# ESPOAT.net
KiCad netlist of a schematic drawn in EAGLE
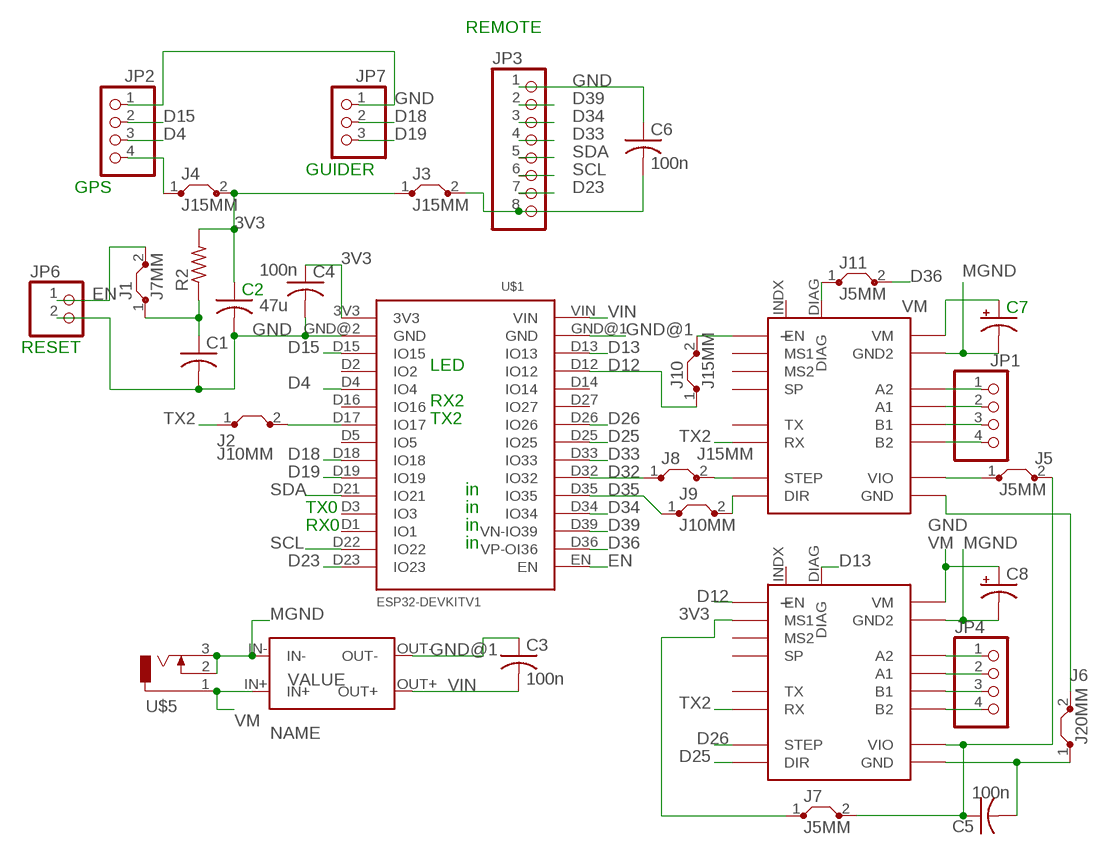
[diagram p0: schematic, sheet 1]

(export (version "E")
  (design (tool "Eeschema 10.0.6"))
  (components
    (comp (ref "C1")
      (value "C-US025-030X050")
      (footprint "eagle-import:C025-030X050")
      (libsource (lib "eagle-import") (part "C-US025-030X050"))
    )
    (comp (ref "C2")
      (value "47u")
      (footprint "eagle-import:C050-024X044")
      (libsource (lib "eagle-import") (part "C-US050-024X044"))
    )
    (comp (ref "C3")
      (value "100n")
      (footprint "eagle-import:C050-024X044")
      (libsource (lib "eagle-import") (part "C-US050-024X044"))
    )
    (comp (ref "C4")
      (value "100n")
      (footprint "eagle-import:C050-024X044")
      (libsource (lib "eagle-import") (part "C-US050-024X044"))
    )
    (comp (ref "C5")
      (value "100n")
      (footprint "eagle-import:C050-024X044")
      (libsource (lib "eagle-import") (part "C-US050-024X044"))
    )
    (comp (ref "C6")
      (value "100n")
      (footprint "eagle-import:C050-024X044")
      (libsource (lib "eagle-import") (part "C-US050-024X044"))
    )
    (comp (ref "C7")
      (value "CPOL-USE5-8.5")
      (footprint "eagle-import:E5-8,5")
      (libsource (lib "eagle-import") (part "CPOL-USE5-8.5"))
    )
    (comp (ref "C8")
      (value "CPOL-USE5-8.5")
      (footprint "eagle-import:E5-8,5")
      (libsource (lib "eagle-import") (part "CPOL-USE5-8.5"))
    )
    (comp (ref "J1")
      (value "J7MM")
      (footprint "eagle-import:07")
      (libsource (lib "eagle-import") (part "J7MM"))
    )
    (comp (ref "J2")
      (value "J10MM")
      (footprint "eagle-import:10")
      (libsource (lib "eagle-import") (part "J10MM"))
    )
    (comp (ref "J3")
      (value "J15MM")
      (footprint "eagle-import:15")
      (libsource (lib "eagle-import") (part "J15MM"))
    )
    (comp (ref "J4")
      (value "J15MM")
      (footprint "eagle-import:15")
      (libsource (lib "eagle-import") (part "J15MM"))
    )
    (comp (ref "J5")
      (value "J5MM")
      (footprint "eagle-import:05")
      (libsource (lib "eagle-import") (part "J5MM"))
    )
    (comp (ref "J6")
      (value "J20MM")
      (footprint "eagle-import:20")
      (libsource (lib "eagle-import") (part "J20MM"))
    )
    (comp (ref "J7")
      (value "J5MM")
      (footprint "eagle-import:05")
      (libsource (lib "eagle-import") (part "J5MM"))
    )
    (comp (ref "J8")
      (value "J15MM")
      (footprint "eagle-import:15")
      (libsource (lib "eagle-import") (part "J15MM"))
    )
    (comp (ref "J9")
      (value "J10MM")
      (footprint "eagle-import:10")
      (libsource (lib "eagle-import") (part "J10MM"))
    )
    (comp (ref "J10")
      (value "J15MM")
      (footprint "eagle-import:15")
      (libsource (lib "eagle-import") (part "J15MM"))
    )
    (comp (ref "J11")
      (value "J5MM")
      (footprint "eagle-import:05")
      (libsource (lib "eagle-import") (part "J5MM"))
    )
    (comp (ref "JP1")
      (value "PINHD-1X4")
      (footprint "eagle-import:1X04")
      (libsource (lib "eagle-import") (part "PINHD-1X4"))
    )
    (comp (ref "JP2")
      (value "PINHD-1X4")
      (footprint "eagle-import:1X04")
      (libsource (lib "eagle-import") (part "PINHD-1X4"))
    )
    (comp (ref "JP3")
      (value "PINHD-1X8")
      (footprint "eagle-import:1X08")
      (libsource (lib "eagle-import") (part "PINHD-1X8"))
    )
    (comp (ref "JP4")
      (value "PINHD-1X4")
      (footprint "eagle-import:1X04")
      (libsource (lib "eagle-import") (part "PINHD-1X4"))
    )
    (comp (ref "JP6")
      (value "PINHD-1X2")
      (footprint "eagle-import:1X02")
      (libsource (lib "eagle-import") (part "PINHD-1X2"))
    )
    (comp (ref "JP7")
      (value "PINHD-1X3")
      (footprint "eagle-import:1X03")
      (libsource (lib "eagle-import") (part "PINHD-1X3"))
    )
    (comp (ref "R2")
      (value "R-US_0207/10")
      (footprint "eagle-import:0207_10")
      (libsource (lib "eagle-import") (part "R-US_0207/10"))
    )
    (comp (ref "U$1")
      (value "ESP32DEVKITV1")
      (footprint "eagle-import:ESP32-DEVKITV1")
      (libsource (lib "eagle-import") (part "ESP32DEVKITV1"))
    )
    (comp (ref "U$2")
      (value "FY2209V3")
      (footprint "eagle-import:FY2209V3")
      (libsource (lib "eagle-import") (part "FY2209V3"))
    )
    (comp (ref "U$3")
      (value "FY2209V3")
      (footprint "eagle-import:FY2209V3")
      (libsource (lib "eagle-import") (part "FY2209V3"))
    )
    (comp (ref "U$4")
      (value "MINI-360")
      (footprint "eagle-import:MINI-360")
      (libsource (lib "eagle-import") (part "MINI-360"))
    )
    (comp (ref "U$5")
      (value "PS0520")
      (footprint "eagle-import:DCJ0203")
      (libsource (lib "eagle-import") (part "PS0520"))
    )
  )
  (nets
    (net (code "1") (name "/3V3") (class "Default")
      (node (ref "C2") (pin "1") (pinfunction "1_1") (pintype "passive"))
      (node (ref "C4") (pin "1") (pinfunction "1_1") (pintype "passive"))
      (node (ref "J3") (pin "1") (pinfunction "1_1") (pintype "passive"))
      (node (ref "J4") (pin "2") (pinfunction "2_2") (pintype "passive"))
      (node (ref "J7") (pin "1") (pinfunction "1_1") (pintype "passive"))
      (node (ref "R2") (pin "2") (pinfunction "2_2") (pintype "passive"))
      (node (ref "U$1") (pin "3V3") (pinfunction "3V3_3V3") (pintype "bidirectional"))
      (node (ref "U$3") (pin "MS1") (pinfunction "MS1_MS1") (pintype "bidirectional"))
    )
    (net (code "2") (name "/D4") (class "Default")
      (node (ref "JP2") (pin "3") (pinfunction "3_3") (pintype "passive"))
      (node (ref "U$1") (pin "D4") (pinfunction "IO4_D4") (pintype "bidirectional"))
    )
    (net (code "3") (name "/D12") (class "Default")
      (node (ref "J10") (pin "1") (pinfunction "1_1") (pintype "passive"))
      (node (ref "U$1") (pin "D12") (pinfunction "IO12_D12") (pintype "bidirectional"))
      (node (ref "U$3") (pin "EN") (pinfunction "EN_EN") (pintype "bidirectional"))
    )
    (net (code "4") (name "/D13") (class "Default")
      (node (ref "U$1") (pin "D13") (pinfunction "IO13_D13") (pintype "bidirectional"))
      (node (ref "U$3") (pin "DIAG") (pinfunction "DIAG_DIAG") (pintype "bidirectional"))
    )
    (net (code "5") (name "/D15") (class "Default")
      (node (ref "JP2") (pin "2") (pinfunction "2_2") (pintype "passive"))
      (node (ref "U$1") (pin "D15") (pinfunction "IO15_D15") (pintype "bidirectional"))
    )
    (net (code "6") (name "/D18") (class "Default")
      (node (ref "JP7") (pin "2") (pinfunction "2_2") (pintype "passive"))
      (node (ref "U$1") (pin "D18") (pinfunction "IO18_D18") (pintype "bidirectional"))
    )
    (net (code "7") (name "/D19") (class "Default")
      (node (ref "JP7") (pin "3") (pinfunction "3_3") (pintype "passive"))
      (node (ref "U$1") (pin "D19") (pinfunction "IO19_D19") (pintype "bidirectional"))
    )
    (net (code "8") (name "/D23") (class "Default")
      (node (ref "JP3") (pin "7") (pinfunction "7_7") (pintype "passive"))
      (node (ref "U$1") (pin "D23") (pinfunction "IO23_D23") (pintype "bidirectional"))
    )
    (net (code "9") (name "/D25") (class "Default")
      (node (ref "U$1") (pin "D25") (pinfunction "IO25_D25") (pintype "bidirectional"))
      (node (ref "U$3") (pin "DIR") (pinfunction "DIR_DIR") (pintype "bidirectional"))
    )
    (net (code "10") (name "/D26") (class "Default")
      (node (ref "U$1") (pin "D26") (pinfunction "IO26_D26") (pintype "bidirectional"))
      (node (ref "U$3") (pin "STP") (pinfunction "STEP_STP") (pintype "bidirectional"))
    )
    (net (code "11") (name "/D32") (class "Default")
      (node (ref "J8") (pin "1") (pinfunction "1_1") (pintype "passive"))
      (node (ref "U$1") (pin "D32") (pinfunction "IO32_D32") (pintype "bidirectional"))
    )
    (net (code "12") (name "/D33") (class "Default")
      (node (ref "JP3") (pin "4") (pinfunction "4_4") (pintype "passive"))
      (node (ref "U$1") (pin "D33") (pinfunction "IO33_D33") (pintype "bidirectional"))
    )
    (net (code "13") (name "/D34") (class "Default")
      (node (ref "JP3") (pin "3") (pinfunction "3_3") (pintype "passive"))
      (node (ref "U$1") (pin "D34") (pinfunction "IO34_D34") (pintype "bidirectional"))
    )
    (net (code "14") (name "/D35") (class "Default")
      (node (ref "J9") (pin "1") (pinfunction "1_1") (pintype "passive"))
      (node (ref "U$1") (pin "D35") (pinfunction "IO35_D35") (pintype "bidirectional"))
    )
    (net (code "15") (name "/D36") (class "Default")
      (node (ref "J11") (pin "2") (pinfunction "2_2") (pintype "passive"))
      (node (ref "U$1") (pin "D36") (pinfunction "VP-OI36_D36") (pintype "bidirectional"))
    )
    (net (code "16") (name "/D39") (class "Default")
      (node (ref "JP3") (pin "2") (pinfunction "2_2") (pintype "passive"))
      (node (ref "U$1") (pin "D39") (pinfunction "VN-IO39_D39") (pintype "bidirectional"))
    )
    (net (code "17") (name "/EN") (class "Default")
      (node (ref "J1") (pin "2") (pinfunction "2_2") (pintype "passive"))
      (node (ref "JP6") (pin "1") (pinfunction "1_1") (pintype "passive"))
      (node (ref "U$1") (pin "EN") (pinfunction "EN_EN") (pintype "bidirectional"))
    )
    (net (code "18") (name "/GND") (class "Default")
      (node (ref "C1") (pin "2") (pinfunction "2_2") (pintype "passive"))
      (node (ref "C2") (pin "2") (pinfunction "2_2") (pintype "passive"))
      (node (ref "C4") (pin "2") (pinfunction "2_2") (pintype "passive"))
      (node (ref "C6") (pin "1") (pinfunction "1_1") (pintype "passive"))
      (node (ref "J6") (pin "2") (pinfunction "2_2") (pintype "passive"))
      (node (ref "JP2") (pin "1") (pinfunction "1_1") (pintype "passive"))
      (node (ref "JP3") (pin "1") (pinfunction "1_1") (pintype "passive"))
      (node (ref "JP6") (pin "2") (pinfunction "2_2") (pintype "passive"))
      (node (ref "JP7") (pin "1") (pinfunction "1_1") (pintype "passive"))
      (node (ref "U$1") (pin "GND@2") (pinfunction "GND_GND@2") (pintype "bidirectional"))
      (node (ref "U$2") (pin "GND") (pinfunction "GND_GND") (pintype "bidirectional"))
    )
    (net (code "19") (name "/GND@1") (class "Default")
      (node (ref "C3") (pin "1") (pinfunction "1_1") (pintype "passive"))
      (node (ref "U$1") (pin "GND@1") (pinfunction "GND_GND@1") (pintype "bidirectional"))
      (node (ref "U$4") (pin "OUT-") (pinfunction "OUT-_OUT-") (pintype "output"))
    )
    (net (code "20") (name "/MGND") (class "Default")
      (node (ref "C7") (pin "-") (pinfunction "-_-") (pintype "passive"))
      (node (ref "C8") (pin "-") (pinfunction "-_-") (pintype "passive"))
      (node (ref "U$2") (pin "GND2") (pinfunction "GND2_GND2") (pintype "bidirectional"))
      (node (ref "U$3") (pin "GND2") (pinfunction "GND2_GND2") (pintype "bidirectional"))
      (node (ref "U$4") (pin "IN-") (pinfunction "IN-_IN-") (pintype "input"))
      (node (ref "U$5") (pin "2") (pinfunction "2_2") (pintype "passive"))
      (node (ref "U$5") (pin "3") (pinfunction "3_3") (pintype "passive"))
    )
    (net (code "21") (name "/SCL") (class "Default")
      (node (ref "JP3") (pin "6") (pinfunction "6_6") (pintype "passive"))
      (node (ref "U$1") (pin "D22") (pinfunction "IO22_D22") (pintype "bidirectional"))
    )
    (net (code "22") (name "/SDA") (class "Default")
      (node (ref "JP3") (pin "5") (pinfunction "5_5") (pintype "passive"))
      (node (ref "U$1") (pin "D21") (pinfunction "IO21_D21") (pintype "bidirectional"))
    )
    (net (code "23") (name "/TX2") (class "Default")
      (node (ref "J2") (pin "1") (pinfunction "1_1") (pintype "passive"))
      (node (ref "U$2") (pin "RX") (pinfunction "RX_RX") (pintype "bidirectional"))
      (node (ref "U$3") (pin "RX") (pinfunction "RX_RX") (pintype "bidirectional"))
    )
    (net (code "24") (name "/VIN") (class "Default")
      (node (ref "C3") (pin "2") (pinfunction "2_2") (pintype "passive"))
      (node (ref "U$1") (pin "VIN") (pinfunction "VIN_VIN") (pintype "bidirectional"))
      (node (ref "U$4") (pin "OUT+") (pinfunction "OUT+_OUT+") (pintype "output"))
    )
    (net (code "25") (name "/VM") (class "Default")
      (node (ref "C7") (pin "+") (pinfunction "+_+") (pintype "passive"))
      (node (ref "C8") (pin "+") (pinfunction "+_+") (pintype "passive"))
      (node (ref "U$2") (pin "VM") (pinfunction "VM_VM") (pintype "bidirectional"))
      (node (ref "U$3") (pin "VM") (pinfunction "VM_VM") (pintype "bidirectional"))
      (node (ref "U$4") (pin "IN+") (pinfunction "IN+_IN+") (pintype "input"))
      (node (ref "U$5") (pin "1") (pinfunction "1_1") (pintype "passive"))
    )
    (net (code "26") (name "Net-(C1-Pad1)") (class "Default")
      (node (ref "C1") (pin "1") (pinfunction "1_1") (pintype "passive"))
      (node (ref "J1") (pin "1") (pinfunction "1_1") (pintype "passive"))
      (node (ref "R2") (pin "1") (pinfunction "1_1") (pintype "passive"))
    )
    (net (code "27") (name "Net-(C5-Pad1)") (class "Default")
      (node (ref "C5") (pin "1") (pinfunction "1_1") (pintype "passive"))
      (node (ref "J5") (pin "2") (pinfunction "2_2") (pintype "passive"))
      (node (ref "J7") (pin "2") (pinfunction "2_2") (pintype "passive"))
      (node (ref "U$3") (pin "VIO") (pinfunction "VIO_VIO") (pintype "bidirectional"))
    )
    (net (code "28") (name "Net-(C5-Pad2)") (class "Default")
      (node (ref "C5") (pin "2") (pinfunction "2_2") (pintype "passive"))
      (node (ref "J6") (pin "1") (pinfunction "1_1") (pintype "passive"))
      (node (ref "U$3") (pin "GND") (pinfunction "GND_GND") (pintype "bidirectional"))
    )
    (net (code "29") (name "Net-(C6-Pad2)") (class "Default")
      (node (ref "C6") (pin "2") (pinfunction "2_2") (pintype "passive"))
      (node (ref "J3") (pin "2") (pinfunction "2_2") (pintype "passive"))
      (node (ref "JP3") (pin "8") (pinfunction "8_8") (pintype "passive"))
    )
    (net (code "30") (name "Net-(J4-Pad1)") (class "Default")
      (node (ref "J4") (pin "1") (pinfunction "1_1") (pintype "passive"))
      (node (ref "JP2") (pin "4") (pinfunction "4_4") (pintype "passive"))
    )
    (net (code "31") (name "Net-(J5-Pad1)") (class "Default")
      (node (ref "J5") (pin "1") (pinfunction "1_1") (pintype "passive"))
      (node (ref "U$2") (pin "VIO") (pinfunction "VIO_VIO") (pintype "bidirectional"))
    )
    (net (code "32") (name "Net-(J9-Pad2)") (class "Default")
      (node (ref "J9") (pin "2") (pinfunction "2_2") (pintype "passive"))
      (node (ref "U$2") (pin "DIR") (pinfunction "DIR_DIR") (pintype "bidirectional"))
    )
    (net (code "33") (name "Net-(J10-Pad2)") (class "Default")
      (node (ref "J10") (pin "2") (pinfunction "2_2") (pintype "passive"))
      (node (ref "U$2") (pin "EN") (pinfunction "EN_EN") (pintype "bidirectional"))
    )
    (net (code "34") (name "Net-(J11-Pad1)") (class "Default")
      (node (ref "J11") (pin "1") (pinfunction "1_1") (pintype "passive"))
      (node (ref "U$2") (pin "DIAG") (pinfunction "DIAG_DIAG") (pintype "bidirectional"))
    )
    (net (code "35") (name "Net-(JP1-Pad1)") (class "Default")
      (node (ref "JP1") (pin "1") (pinfunction "1_1") (pintype "passive"))
      (node (ref "U$2") (pin "A2") (pinfunction "A2_A2") (pintype "bidirectional"))
    )
    (net (code "36") (name "Net-(JP1-Pad2)") (class "Default")
      (node (ref "JP1") (pin "2") (pinfunction "2_2") (pintype "passive"))
      (node (ref "U$2") (pin "A1") (pinfunction "A1_A1") (pintype "bidirectional"))
    )
    (net (code "37") (name "Net-(JP1-Pad3)") (class "Default")
      (node (ref "JP1") (pin "3") (pinfunction "3_3") (pintype "passive"))
      (node (ref "U$2") (pin "B1") (pinfunction "B1_B1") (pintype "bidirectional"))
    )
    (net (code "38") (name "Net-(JP1-Pad4)") (class "Default")
      (node (ref "JP1") (pin "4") (pinfunction "4_4") (pintype "passive"))
      (node (ref "U$2") (pin "B2") (pinfunction "B2_B2") (pintype "bidirectional"))
    )
    (net (code "39") (name "Net-(JP4-Pad1)") (class "Default")
      (node (ref "JP4") (pin "1") (pinfunction "1_1") (pintype "passive"))
      (node (ref "U$3") (pin "A2") (pinfunction "A2_A2") (pintype "bidirectional"))
    )
    (net (code "40") (name "Net-(JP4-Pad2)") (class "Default")
      (node (ref "JP4") (pin "2") (pinfunction "2_2") (pintype "passive"))
      (node (ref "U$3") (pin "A1") (pinfunction "A1_A1") (pintype "bidirectional"))
    )
    (net (code "41") (name "Net-(JP4-Pad3)") (class "Default")
      (node (ref "JP4") (pin "3") (pinfunction "3_3") (pintype "passive"))
      (node (ref "U$3") (pin "B1") (pinfunction "B1_B1") (pintype "bidirectional"))
    )
    (net (code "42") (name "Net-(JP4-Pad4)") (class "Default")
      (node (ref "JP4") (pin "4") (pinfunction "4_4") (pintype "passive"))
      (node (ref "U$3") (pin "B2") (pinfunction "B2_B2") (pintype "bidirectional"))
    )
    (net (code "43") (name "Net-(U$1-IO17)") (class "Default")
      (node (ref "J2") (pin "2") (pinfunction "2_2") (pintype "passive"))
      (node (ref "U$1") (pin "D17") (pinfunction "IO17_D17") (pintype "bidirectional"))
    )
    (net (code "44") (name "Net-(U$2-STEP)") (class "Default")
      (node (ref "J8") (pin "2") (pinfunction "2_2") (pintype "passive"))
      (node (ref "U$2") (pin "STP") (pinfunction "STEP_STP") (pintype "bidirectional"))
    )
    (net (code "45") (name "unconnected-(U$1-IO1-PadD1)") (class "Default")
      (node (ref "U$1") (pin "D1") (pinfunction "IO1_D1") (pintype "bidirectional"))
    )
    (net (code "46") (name "unconnected-(U$1-IO2-PadD2)") (class "Default")
      (node (ref "U$1") (pin "D2") (pinfunction "IO2_D2") (pintype "bidirectional"))
    )
    (net (code "47") (name "unconnected-(U$1-IO3-PadD3)") (class "Default")
      (node (ref "U$1") (pin "D3") (pinfunction "IO3_D3") (pintype "bidirectional"))
    )
    (net (code "48") (name "unconnected-(U$1-IO5-PadD5)") (class "Default")
      (node (ref "U$1") (pin "D5") (pinfunction "IO5_D5") (pintype "bidirectional"))
    )
    (net (code "49") (name "unconnected-(U$1-IO14-PadD14)") (class "Default")
      (node (ref "U$1") (pin "D14") (pinfunction "IO14_D14") (pintype "bidirectional"))
    )
    (net (code "50") (name "unconnected-(U$1-IO16-PadD16)") (class "Default")
      (node (ref "U$1") (pin "D16") (pinfunction "IO16_D16") (pintype "bidirectional"))
    )
    (net (code "51") (name "unconnected-(U$1-IO27-PadD27)") (class "Default")
      (node (ref "U$1") (pin "D27") (pinfunction "IO27_D27") (pintype "bidirectional"))
    )
    (net (code "52") (name "unconnected-(U$2-I-PadINDX)") (class "Default")
      (node (ref "U$2") (pin "INDX") (pinfunction "I_INDX") (pintype "bidirectional"))
    )
    (net (code "53") (name "unconnected-(U$2-PadMS1)") (class "Default")
      (node (ref "U$2") (pin "MS1") (pinfunction "MS1_MS1") (pintype "bidirectional"))
    )
    (net (code "54") (name "unconnected-(U$2-PadMS2)") (class "Default")
      (node (ref "U$2") (pin "MS2") (pinfunction "MS2_MS2") (pintype "bidirectional"))
    )
    (net (code "55") (name "unconnected-(U$2-PadSP)") (class "Default")
      (node (ref "U$2") (pin "SP") (pinfunction "SP_SP") (pintype "bidirectional"))
    )
    (net (code "56") (name "unconnected-(U$2-PadTX)") (class "Default")
      (node (ref "U$2") (pin "TX") (pinfunction "TX_TX") (pintype "bidirectional"))
    )
    (net (code "57") (name "unconnected-(U$3-I-PadINDX)") (class "Default")
      (node (ref "U$3") (pin "INDX") (pinfunction "I_INDX") (pintype "bidirectional"))
    )
    (net (code "58") (name "unconnected-(U$3-PadMS2)") (class "Default")
      (node (ref "U$3") (pin "MS2") (pinfunction "MS2_MS2") (pintype "bidirectional"))
    )
    (net (code "59") (name "unconnected-(U$3-PadSP)") (class "Default")
      (node (ref "U$3") (pin "SP") (pinfunction "SP_SP") (pintype "bidirectional"))
    )
    (net (code "60") (name "unconnected-(U$3-PadTX)") (class "Default")
      (node (ref "U$3") (pin "TX") (pinfunction "TX_TX") (pintype "bidirectional"))
    )
  )
)
